# Adafruit_INA237_Power_Monitor_PCB.net
KiCad netlist of a schematic drawn in EAGLE
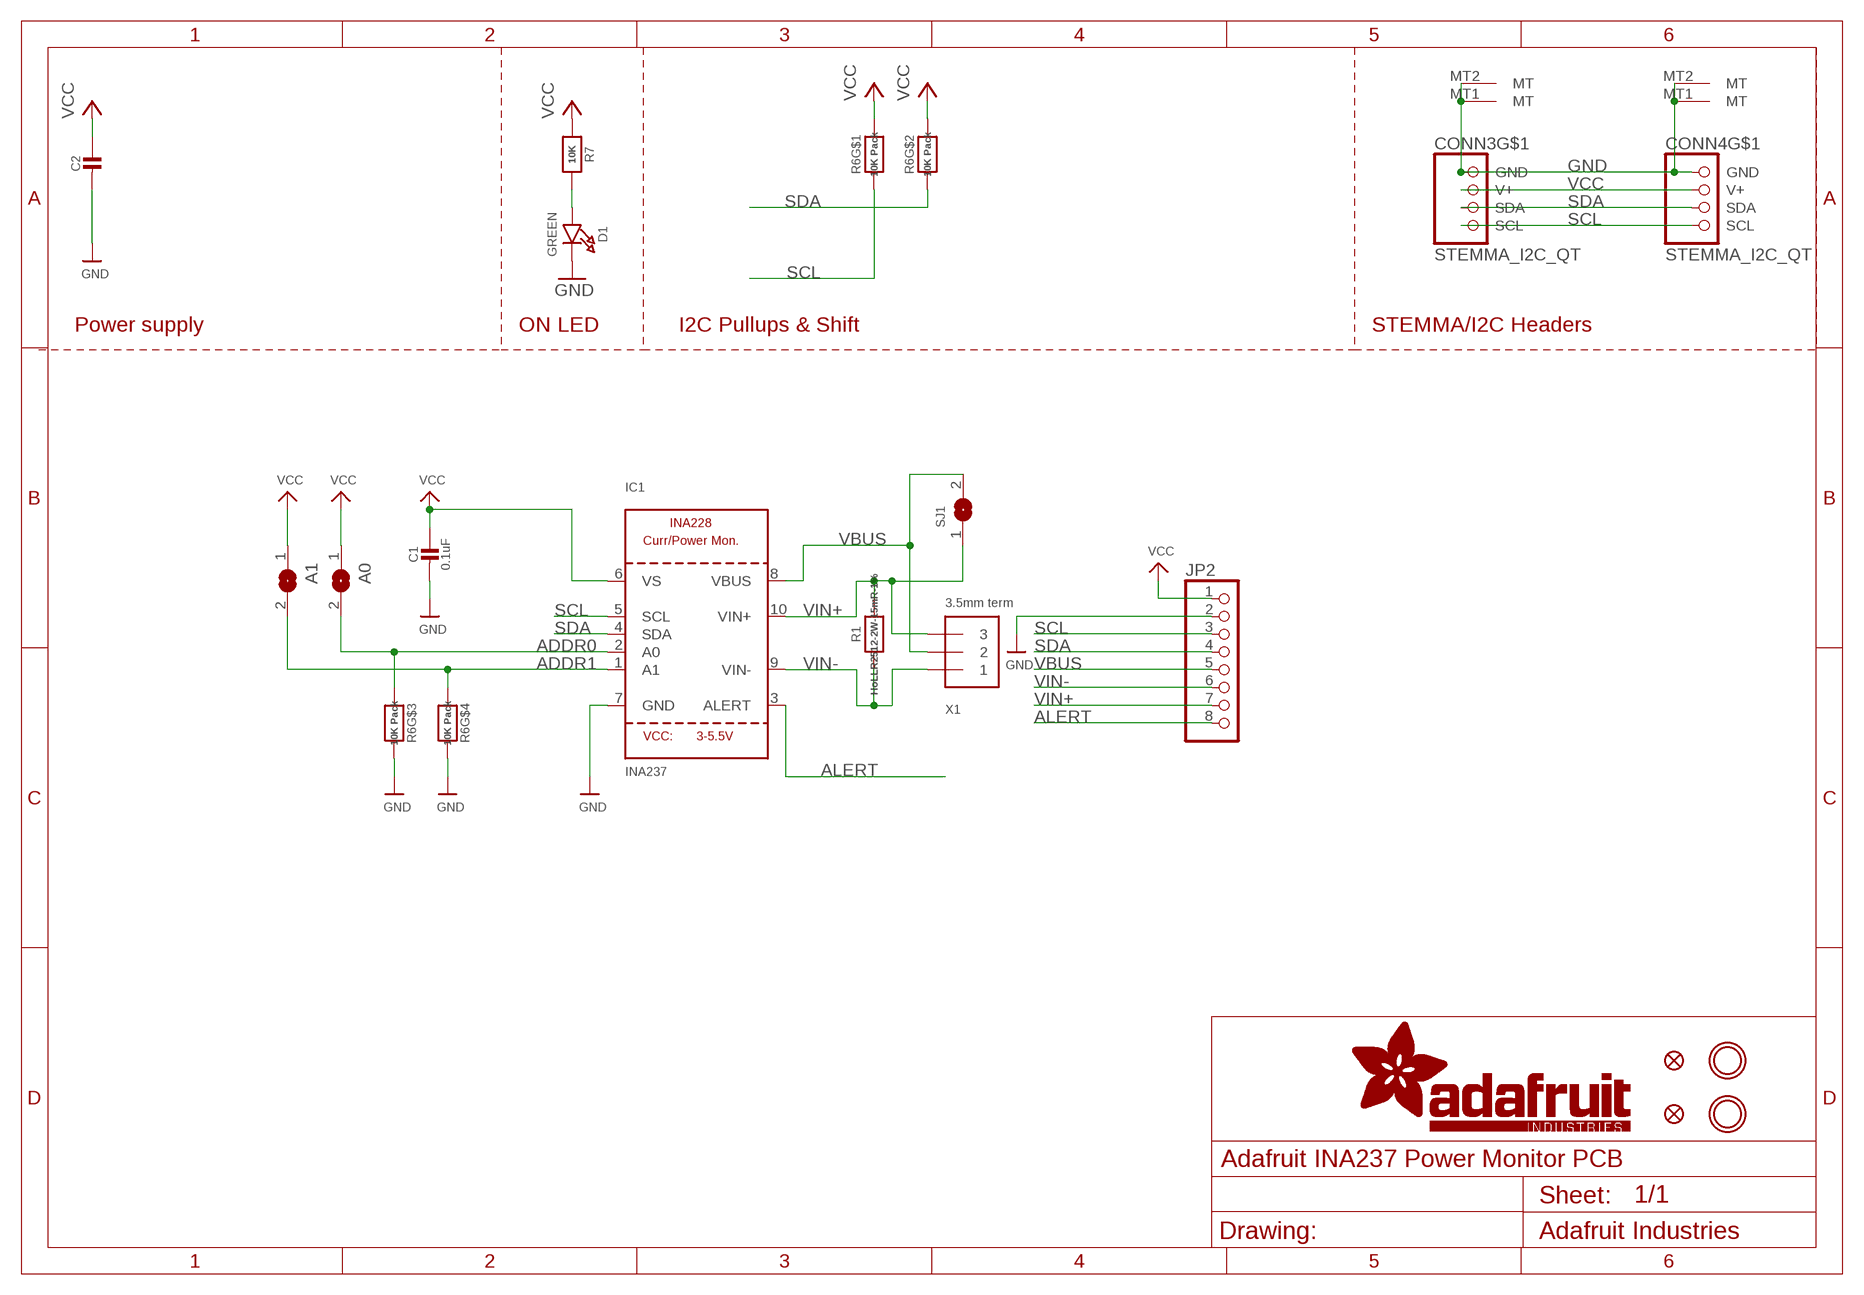
[diagram p0: schematic, sheet 1]

(export (version "E")
  (design (tool "Eeschema 10.0.6"))
  (components
    (comp (ref "A0")
      (value "SOLDERJUMPERREFLOW_NOPASTE")
      (footprint "eagle-import:SOLDERJUMPER_REFLOW_NOPASTE")
      (libsource (lib "eagle-import") (part "SOLDERJUMPERREFLOW_NOPASTE"))
    )
    (comp (ref "A1")
      (value "SOLDERJUMPERREFLOW_NOPASTE")
      (footprint "eagle-import:SOLDERJUMPER_REFLOW_NOPASTE")
      (libsource (lib "eagle-import") (part "SOLDERJUMPERREFLOW_NOPASTE"))
    )
    (comp (ref "C1")
      (value "0.1uF")
      (footprint "eagle-import:0603-NO")
      (libsource (lib "eagle-import") (part "CAP_CERAMIC0603_NO"))
    )
    (comp (ref "C2")
      (value "10uF")
      (footprint "eagle-import:0805-NO")
      (libsource (lib "eagle-import") (part "CAP_CERAMIC0805-NOOUTLINE"))
    )
    (comp (ref "CONN3")
      (value "STEMMA_I2C_QT")
      (footprint "eagle-import:JST_SH4")
      (libsource (lib "eagle-import") (part "STEMMA_I2C_QT"))
    )
    (comp (ref "CONN4")
      (value "STEMMA_I2C_QT")
      (footprint "eagle-import:JST_SH4")
      (libsource (lib "eagle-import") (part "STEMMA_I2C_QT"))
    )
    (comp (ref "D1")
      (value "GREEN")
      (footprint "eagle-import:CHIPLED_0603_NOOUTLINE")
      (libsource (lib "eagle-import") (part "LED0603_NOOUTLINE"))
    )
    (comp (ref "FID3")
      (value "FIDUCIAL_1MM")
      (footprint "eagle-import:FIDUCIAL_1MM")
      (libsource (lib "eagle-import") (part "FIDUCIAL_1MM"))
    )
    (comp (ref "FID4")
      (value "FIDUCIAL_1MM")
      (footprint "eagle-import:FIDUCIAL_1MM")
      (libsource (lib "eagle-import") (part "FIDUCIAL_1MM"))
    )
    (comp (ref "IC1")
      (value "INA237")
      (footprint "eagle-import:MSOP10")
      (libsource (lib "eagle-import") (part "INA228"))
    )
    (comp (ref "JP2")
      (value "HEADER-1X870MIL")
      (footprint "eagle-import:1X08_ROUND_70")
      (libsource (lib "eagle-import") (part "HEADER-1X870MIL"))
    )
    (comp (ref "R1")
      (value "HoLLR2512-2W-15mR-1%")
      (footprint "eagle-import:2512")
      (libsource (lib "eagle-import") (part "RESISTOR2512"))
    )
    (comp (ref "R6")
      (value "10K Pack")
      (footprint "eagle-import:RESPACK_4X0603")
      (libsource (lib "eagle-import") (part "RESISTOR_4PACK"))
    )
    (comp (ref "R7")
      (value "10K")
      (footprint "eagle-import:0603-NO")
      (libsource (lib "eagle-import") (part "RESISTOR_0603_NOOUT"))
    )
    (comp (ref "SJ1")
      (value "SOLDERJUMPERCLOSED")
      (footprint "eagle-import:SOLDERJUMPER_CLOSEDWIRE")
      (libsource (lib "eagle-import") (part "SOLDERJUMPERCLOSED"))
    )
    (comp (ref "U$20")
      (value "MOUNTINGHOLE2.5")
      (footprint "eagle-import:MOUNTINGHOLE_2.5_PLATED")
      (libsource (lib "eagle-import") (part "MOUNTINGHOLE2.5"))
    )
    (comp (ref "U$21")
      (value "MOUNTINGHOLE2.5")
      (footprint "eagle-import:MOUNTINGHOLE_2.5_PLATED")
      (libsource (lib "eagle-import") (part "MOUNTINGHOLE2.5"))
    )
    (comp (ref "X1")
      (value "3.5mm term")
      (footprint "eagle-import:TERMBLOCK_1X3-3.5MM")
      (libsource (lib "eagle-import") (part "TERMBLOCK_1X3"))
    )
  )
  (nets
    (net (code "1") (name "/ADDR0") (class "Default")
      (node (ref "A0") (pin "2") (pinfunction "2_2") (pintype "passive"))
      (node (ref "IC1") (pin "2") (pinfunction "A0_2") (pintype "input"))
      (node (ref "R6") (pin "3") (pinfunction "1_3") (pintype "passive"))
    )
    (net (code "2") (name "/ADDR1") (class "Default")
      (node (ref "A1") (pin "2") (pinfunction "2_2") (pintype "passive"))
      (node (ref "IC1") (pin "1") (pinfunction "A1_1") (pintype "input"))
      (node (ref "R6") (pin "4") (pinfunction "1_4") (pintype "passive"))
    )
    (net (code "3") (name "/ALERT") (class "Default")
      (node (ref "IC1") (pin "3") (pinfunction "ALERT_3") (pintype "output"))
      (node (ref "JP2") (pin "8") (pinfunction "8_8") (pintype "passive"))
    )
    (net (code "4") (name "/SCL") (class "Default")
      (node (ref "CONN3") (pin "4") (pinfunction "SCL_4") (pintype "passive"))
      (node (ref "CONN4") (pin "4") (pinfunction "SCL_4") (pintype "passive"))
      (node (ref "IC1") (pin "5") (pinfunction "SCL_5") (pintype "bidirectional"))
      (node (ref "JP2") (pin "3") (pinfunction "3_3") (pintype "passive"))
      (node (ref "R6") (pin "1") (pinfunction "1_1") (pintype "passive"))
    )
    (net (code "5") (name "/SDA") (class "Default")
      (node (ref "CONN3") (pin "3") (pinfunction "SDA_3") (pintype "passive"))
      (node (ref "CONN4") (pin "3") (pinfunction "SDA_3") (pintype "passive"))
      (node (ref "IC1") (pin "4") (pinfunction "SDA_4") (pintype "bidirectional"))
      (node (ref "JP2") (pin "4") (pinfunction "4_4") (pintype "passive"))
      (node (ref "R6") (pin "2") (pinfunction "1_2") (pintype "passive"))
    )
    (net (code "6") (name "/VBUS") (class "Default")
      (node (ref "IC1") (pin "8") (pinfunction "VBUS_8") (pintype "power_in"))
      (node (ref "JP2") (pin "5") (pinfunction "5_5") (pintype "passive"))
      (node (ref "SJ1") (pin "2") (pinfunction "2_2") (pintype "passive"))
      (node (ref "X1") (pin "2") (pinfunction "2_2") (pintype "passive"))
    )
    (net (code "7") (name "/VIN+") (class "Default")
      (node (ref "IC1") (pin "10") (pinfunction "VIN+_10") (pintype "bidirectional"))
      (node (ref "JP2") (pin "7") (pinfunction "7_7") (pintype "passive"))
      (node (ref "R1") (pin "2") (pinfunction "2_2") (pintype "passive"))
      (node (ref "SJ1") (pin "1") (pinfunction "1_1") (pintype "passive"))
      (node (ref "X1") (pin "3") (pinfunction "3_3") (pintype "passive"))
    )
    (net (code "8") (name "/VIN-") (class "Default")
      (node (ref "IC1") (pin "9") (pinfunction "VIN-_9") (pintype "bidirectional"))
      (node (ref "JP2") (pin "6") (pinfunction "6_6") (pintype "passive"))
      (node (ref "R1") (pin "1") (pinfunction "1_1") (pintype "passive"))
      (node (ref "X1") (pin "1") (pinfunction "1_1") (pintype "passive"))
    )
    (net (code "9") (name "GND") (class "Default")
      (node (ref "C1") (pin "2") (pinfunction "2_2") (pintype "passive"))
      (node (ref "C2") (pin "2") (pinfunction "2_2") (pintype "passive"))
      (node (ref "CONN3") (pin "1") (pinfunction "GND_1") (pintype "passive"))
      (node (ref "CONN3") (pin "MT1") (pinfunction "MT_MT1") (pintype "bidirectional"))
      (node (ref "CONN3") (pin "MT2") (pinfunction "MT_MT2") (pintype "bidirectional"))
      (node (ref "CONN4") (pin "1") (pinfunction "GND_1") (pintype "passive"))
      (node (ref "CONN4") (pin "MT1") (pinfunction "MT_MT1") (pintype "bidirectional"))
      (node (ref "CONN4") (pin "MT2") (pinfunction "MT_MT2") (pintype "bidirectional"))
      (node (ref "D1") (pin "C") (pinfunction "C_C") (pintype "passive"))
      (node (ref "IC1") (pin "7") (pinfunction "GND_7") (pintype "power_in"))
      (node (ref "JP2") (pin "2") (pinfunction "2_2") (pintype "passive"))
      (node (ref "R6") (pin "5") (pinfunction "2_5") (pintype "passive"))
      (node (ref "R6") (pin "6") (pinfunction "2_6") (pintype "passive"))
    )
    (net (code "10") (name "Net-(D1-PadA)") (class "Default")
      (node (ref "D1") (pin "A") (pinfunction "A_A") (pintype "passive"))
      (node (ref "R7") (pin "2") (pinfunction "2_2") (pintype "passive"))
    )
    (net (code "11") (name "VCC") (class "Default")
      (node (ref "A0") (pin "1") (pinfunction "1_1") (pintype "passive"))
      (node (ref "A1") (pin "1") (pinfunction "1_1") (pintype "passive"))
      (node (ref "C1") (pin "1") (pinfunction "1_1") (pintype "passive"))
      (node (ref "C2") (pin "1") (pinfunction "1_1") (pintype "passive"))
      (node (ref "CONN3") (pin "2") (pinfunction "V+_2") (pintype "passive"))
      (node (ref "CONN4") (pin "2") (pinfunction "V+_2") (pintype "passive"))
      (node (ref "IC1") (pin "6") (pinfunction "VS_6") (pintype "power_in"))
      (node (ref "JP2") (pin "1") (pinfunction "1_1") (pintype "passive"))
      (node (ref "R6") (pin "7") (pinfunction "2_7") (pintype "passive"))
      (node (ref "R6") (pin "8") (pinfunction "2_8") (pintype "passive"))
      (node (ref "R7") (pin "1") (pinfunction "1_1") (pintype "passive"))
    )
  )
)
